# schematic.net
KiCad netlist of a schematic drawn in EAGLE
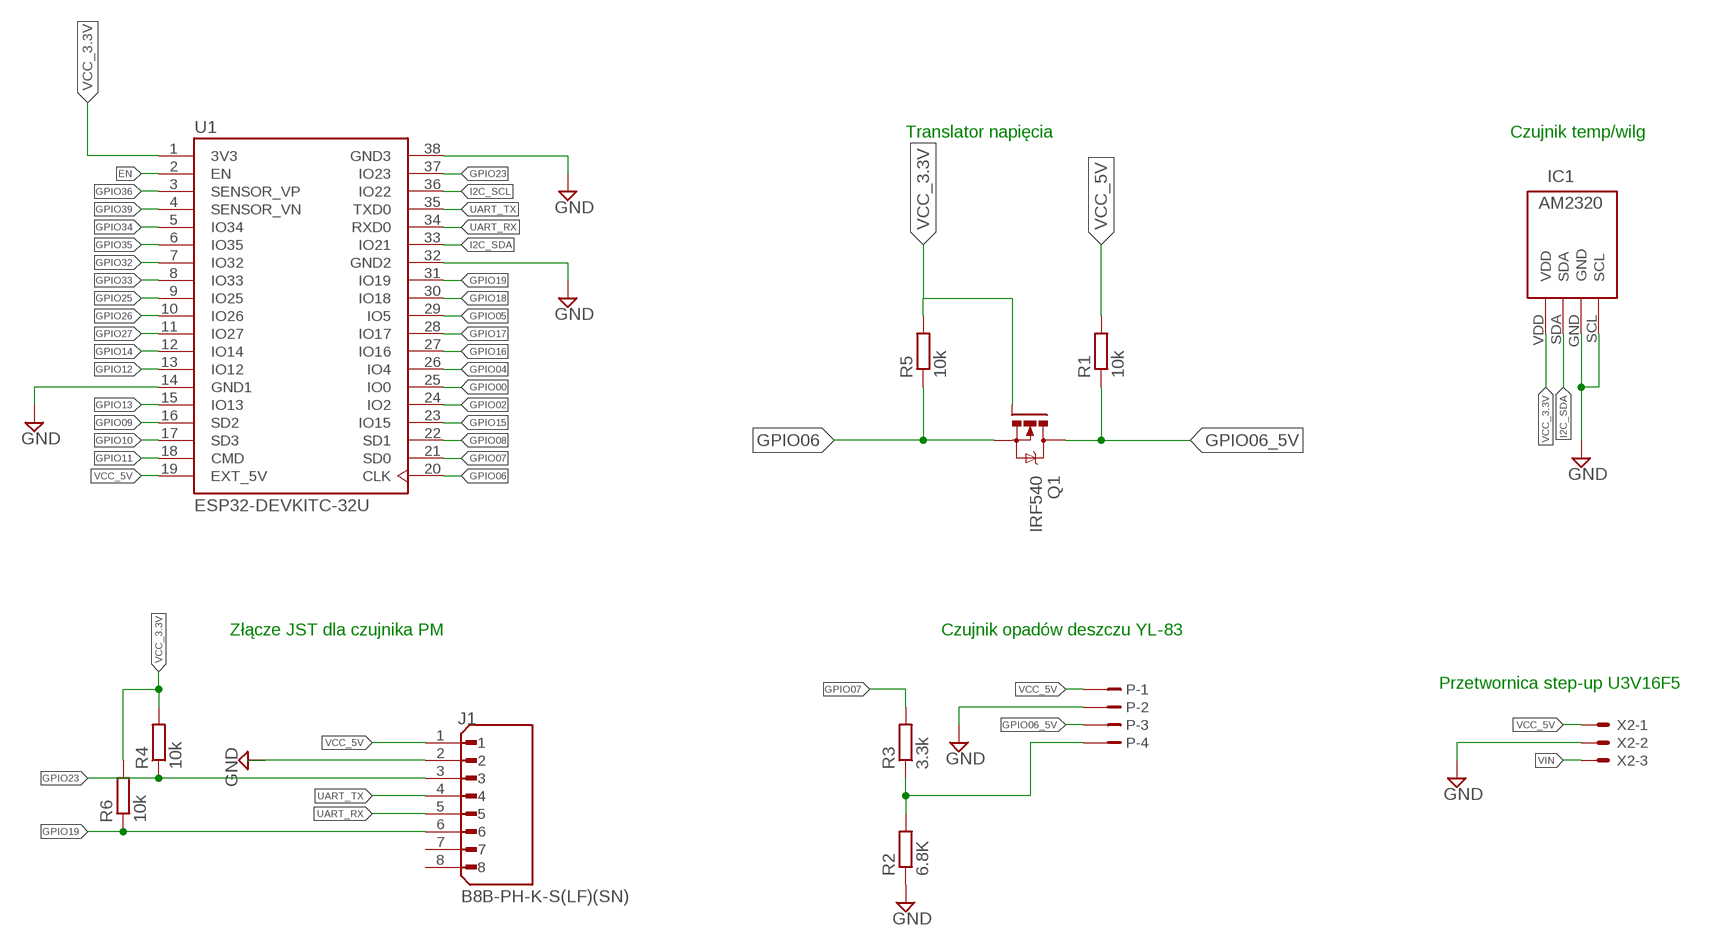
[diagram p0: schematic, sheet 1]

(export (version "E")
  (design (tool "Eeschema 10.0.6"))
  (components
    (comp (ref "IC1")
      (value "AM2320")
      (footprint "eagle-import:AM2320")
      (libsource (lib "eagle-import") (part "AM2320"))
    )
    (comp (ref "J1")
      (value "B8B-PH-K-S(LF)(SN)")
      (footprint "eagle-import:JST_B8B-PH-K-S(LF)(SN)")
      (fields (field (name "MF") "JST Sales"))
      (libsource (lib "eagle-import") (part "B8B-PH-K-S(LF)(SN)"))
    )
    (comp (ref "P")
      (value "B4B-ZR")
      (footprint "eagle-import:B4B-ZR")
      (fields (field (name "MF") "FARNELL") (field (name "MPN") "B4B-ZR(LF)(SN)"))
      (libsource (lib "eagle-import") (part "?4B-ZRB"))
    )
    (comp (ref "Q1")
      (value "IRF540")
      (footprint "eagle-import:TO220BV")
      (libsource (lib "eagle-import") (part "IRF540"))
    )
    (comp (ref "R1")
      (value "10k")
      (footprint "eagle-import:0204V")
      (libsource (lib "eagle-import") (part "R-EU_0204/2V"))
    )
    (comp (ref "R2")
      (value "6.8K")
      (footprint "eagle-import:0204V")
      (libsource (lib "eagle-import") (part "R-EU_0204/2V"))
    )
    (comp (ref "R3")
      (value "3.3k")
      (footprint "eagle-import:0204V")
      (libsource (lib "eagle-import") (part "R-EU_0204/2V"))
    )
    (comp (ref "R4")
      (value "10k")
      (footprint "eagle-import:0204V")
      (libsource (lib "eagle-import") (part "R-EU_0204/2V"))
    )
    (comp (ref "R5")
      (value "10k")
      (footprint "eagle-import:0204V")
      (libsource (lib "eagle-import") (part "R-EU_0204/2V"))
    )
    (comp (ref "R6")
      (value "10k")
      (footprint "eagle-import:0204V")
      (libsource (lib "eagle-import") (part "R-EU_0204/2V"))
    )
    (comp (ref "U1")
      (value "ESP32-DEVKITC-32U")
      (footprint "eagle-import:MODULE_ESP32-DEVKITC-32U")
      (fields (field (name "MANUFACTURER") "Espressif Systems"))
      (libsource (lib "eagle-import") (part "ESP32-DEVKITC-32U"))
    )
    (comp (ref "X2")
      (value "22-23-2031")
      (footprint "eagle-import:22-23-2031")
      (fields (field (name "MF") "MOLEX"))
      (libsource (lib "eagle-import") (part "22-23-2031"))
    )
  )
  (nets
    (net (code "1") (name "EN") (class "Default")
      (node (ref "U1") (pin "2") (pinfunction "EN_2") (pintype "input"))
    )
    (net (code "2") (name "GND") (class "Default")
      (node (ref "IC1") (pin "GND") (pinfunction "GND_GND") (pintype "power_in"))
      (node (ref "IC1") (pin "SCL") (pinfunction "SCL_SCL") (pintype "bidirectional"))
      (node (ref "J1") (pin "2") (pinfunction "2_2") (pintype "passive"))
      (node (ref "P") (pin "2") (pinfunction "1_2") (pintype "passive"))
      (node (ref "R2") (pin "1") (pinfunction "1_1") (pintype "passive"))
      (node (ref "U1") (pin "14") (pinfunction "GND1_14") (pintype "power_in"))
      (node (ref "U1") (pin "32") (pinfunction "GND2_32") (pintype "power_in"))
      (node (ref "U1") (pin "38") (pinfunction "GND3_38") (pintype "power_in"))
      (node (ref "X2") (pin "2") (pinfunction "S_2") (pintype "passive"))
    )
    (net (code "3") (name "GPIO00") (class "Default")
      (node (ref "U1") (pin "25") (pinfunction "IO0_25") (pintype "bidirectional"))
    )
    (net (code "4") (name "GPIO02") (class "Default")
      (node (ref "U1") (pin "24") (pinfunction "IO2_24") (pintype "bidirectional"))
    )
    (net (code "5") (name "GPIO04") (class "Default")
      (node (ref "U1") (pin "26") (pinfunction "IO4_26") (pintype "bidirectional"))
    )
    (net (code "6") (name "GPIO05") (class "Default")
      (node (ref "U1") (pin "29") (pinfunction "IO5_29") (pintype "bidirectional"))
    )
    (net (code "7") (name "GPIO06") (class "Default")
      (node (ref "Q1") (pin "S") (pinfunction "S_S") (pintype "passive"))
      (node (ref "R5") (pin "1") (pinfunction "1_1") (pintype "passive"))
      (node (ref "U1") (pin "20") (pinfunction "CLK_20") (pintype "input"))
    )
    (net (code "8") (name "GPIO06_5V") (class "Default")
      (node (ref "P") (pin "3") (pinfunction "1_3") (pintype "passive"))
      (node (ref "Q1") (pin "D") (pinfunction "D_D") (pintype "passive"))
      (node (ref "R1") (pin "1") (pinfunction "1_1") (pintype "passive"))
    )
    (net (code "9") (name "GPIO07") (class "Default")
      (node (ref "R3") (pin "2") (pinfunction "2_2") (pintype "passive"))
      (node (ref "U1") (pin "21") (pinfunction "SD0_21") (pintype "bidirectional"))
    )
    (net (code "10") (name "GPIO08") (class "Default")
      (node (ref "U1") (pin "22") (pinfunction "SD1_22") (pintype "bidirectional"))
    )
    (net (code "11") (name "GPIO09") (class "Default")
      (node (ref "U1") (pin "16") (pinfunction "SD2_16") (pintype "bidirectional"))
    )
    (net (code "12") (name "GPIO10") (class "Default")
      (node (ref "U1") (pin "17") (pinfunction "SD3_17") (pintype "bidirectional"))
    )
    (net (code "13") (name "GPIO11") (class "Default")
      (node (ref "U1") (pin "18") (pinfunction "CMD_18") (pintype "bidirectional"))
    )
    (net (code "14") (name "GPIO12") (class "Default")
      (node (ref "U1") (pin "13") (pinfunction "IO12_13") (pintype "bidirectional"))
    )
    (net (code "15") (name "GPIO13") (class "Default")
      (node (ref "U1") (pin "15") (pinfunction "IO13_15") (pintype "bidirectional"))
    )
    (net (code "16") (name "GPIO14") (class "Default")
      (node (ref "U1") (pin "12") (pinfunction "IO14_12") (pintype "bidirectional"))
    )
    (net (code "17") (name "GPIO15") (class "Default")
      (node (ref "U1") (pin "23") (pinfunction "IO15_23") (pintype "bidirectional"))
    )
    (net (code "18") (name "GPIO16") (class "Default")
      (node (ref "U1") (pin "27") (pinfunction "IO16_27") (pintype "bidirectional"))
    )
    (net (code "19") (name "GPIO17") (class "Default")
      (node (ref "U1") (pin "28") (pinfunction "IO17_28") (pintype "bidirectional"))
    )
    (net (code "20") (name "GPIO18") (class "Default")
      (node (ref "U1") (pin "30") (pinfunction "IO18_30") (pintype "bidirectional"))
    )
    (net (code "21") (name "GPIO19") (class "Default")
      (node (ref "J1") (pin "6") (pinfunction "6_6") (pintype "passive"))
      (node (ref "R6") (pin "1") (pinfunction "1_1") (pintype "passive"))
      (node (ref "U1") (pin "31") (pinfunction "IO19_31") (pintype "bidirectional"))
    )
    (net (code "22") (name "GPIO23") (class "Default")
      (node (ref "J1") (pin "3") (pinfunction "3_3") (pintype "passive"))
      (node (ref "R4") (pin "1") (pinfunction "1_1") (pintype "passive"))
      (node (ref "U1") (pin "37") (pinfunction "IO23_37") (pintype "bidirectional"))
    )
    (net (code "23") (name "GPIO25") (class "Default")
      (node (ref "U1") (pin "9") (pinfunction "IO25_9") (pintype "bidirectional"))
    )
    (net (code "24") (name "GPIO26") (class "Default")
      (node (ref "U1") (pin "10") (pinfunction "IO26_10") (pintype "bidirectional"))
    )
    (net (code "25") (name "GPIO27") (class "Default")
      (node (ref "U1") (pin "11") (pinfunction "IO27_11") (pintype "bidirectional"))
    )
    (net (code "26") (name "GPIO32") (class "Default")
      (node (ref "U1") (pin "7") (pinfunction "IO32_7") (pintype "bidirectional"))
    )
    (net (code "27") (name "GPIO33") (class "Default")
      (node (ref "U1") (pin "8") (pinfunction "IO33_8") (pintype "bidirectional"))
    )
    (net (code "28") (name "GPIO34") (class "Default")
      (node (ref "U1") (pin "5") (pinfunction "IO34_5") (pintype "bidirectional"))
    )
    (net (code "29") (name "GPIO35") (class "Default")
      (node (ref "U1") (pin "6") (pinfunction "IO35_6") (pintype "bidirectional"))
    )
    (net (code "30") (name "GPIO36") (class "Default")
      (node (ref "U1") (pin "3") (pinfunction "SENSOR_VP_3") (pintype "input"))
    )
    (net (code "31") (name "GPIO39") (class "Default")
      (node (ref "U1") (pin "4") (pinfunction "SENSOR_VN_4") (pintype "input"))
    )
    (net (code "32") (name "I2C_SCL") (class "Default")
      (node (ref "U1") (pin "36") (pinfunction "IO22_36") (pintype "bidirectional"))
    )
    (net (code "33") (name "I2C_SDA") (class "Default")
      (node (ref "IC1") (pin "SDA") (pinfunction "SDA_SDA") (pintype "bidirectional"))
      (node (ref "U1") (pin "33") (pinfunction "IO21_33") (pintype "bidirectional"))
    )
    (net (code "34") (name "Net-(PD-1)") (class "Default")
      (node (ref "P") (pin "4") (pinfunction "1_4") (pintype "passive"))
      (node (ref "R2") (pin "2") (pinfunction "2_2") (pintype "passive"))
      (node (ref "R3") (pin "1") (pinfunction "1_1") (pintype "passive"))
    )
    (net (code "35") (name "UART_RX") (class "Default")
      (node (ref "J1") (pin "5") (pinfunction "5_5") (pintype "passive"))
      (node (ref "U1") (pin "34") (pinfunction "RXD0_34") (pintype "input"))
    )
    (net (code "36") (name "UART_TX") (class "Default")
      (node (ref "J1") (pin "4") (pinfunction "4_4") (pintype "passive"))
      (node (ref "U1") (pin "35") (pinfunction "TXD0_35") (pintype "output"))
    )
    (net (code "37") (name "VCC_3.3V") (class "Default")
      (node (ref "IC1") (pin "VDD") (pinfunction "VDD_VDD") (pintype "power_in"))
      (node (ref "Q1") (pin "G") (pinfunction "G_G") (pintype "passive"))
      (node (ref "R4") (pin "2") (pinfunction "2_2") (pintype "passive"))
      (node (ref "R5") (pin "2") (pinfunction "2_2") (pintype "passive"))
      (node (ref "R6") (pin "2") (pinfunction "2_2") (pintype "passive"))
      (node (ref "U1") (pin "1") (pinfunction "3V3_1") (pintype "power_in"))
    )
    (net (code "38") (name "VCC_5V") (class "Default")
      (node (ref "J1") (pin "1") (pinfunction "1_1") (pintype "passive"))
      (node (ref "P") (pin "1") (pinfunction "1_1") (pintype "passive"))
      (node (ref "R1") (pin "2") (pinfunction "2_2") (pintype "passive"))
      (node (ref "U1") (pin "19") (pinfunction "EXT_5V_19") (pintype "power_in"))
      (node (ref "X2") (pin "1") (pinfunction "S_1") (pintype "passive"))
    )
    (net (code "39") (name "VIN") (class "Default")
      (node (ref "X2") (pin "3") (pinfunction "S_3") (pintype "passive"))
    )
    (net (code "40") (name "unconnected-(J1-Pad7)") (class "Default")
      (node (ref "J1") (pin "7") (pinfunction "7_7") (pintype "passive"))
    )
    (net (code "41") (name "unconnected-(J1-Pad8)") (class "Default")
      (node (ref "J1") (pin "8") (pinfunction "8_8") (pintype "passive"))
    )
  )
)
